# Peripherals.net
KiCad netlist of a schematic drawn in Altium Designer
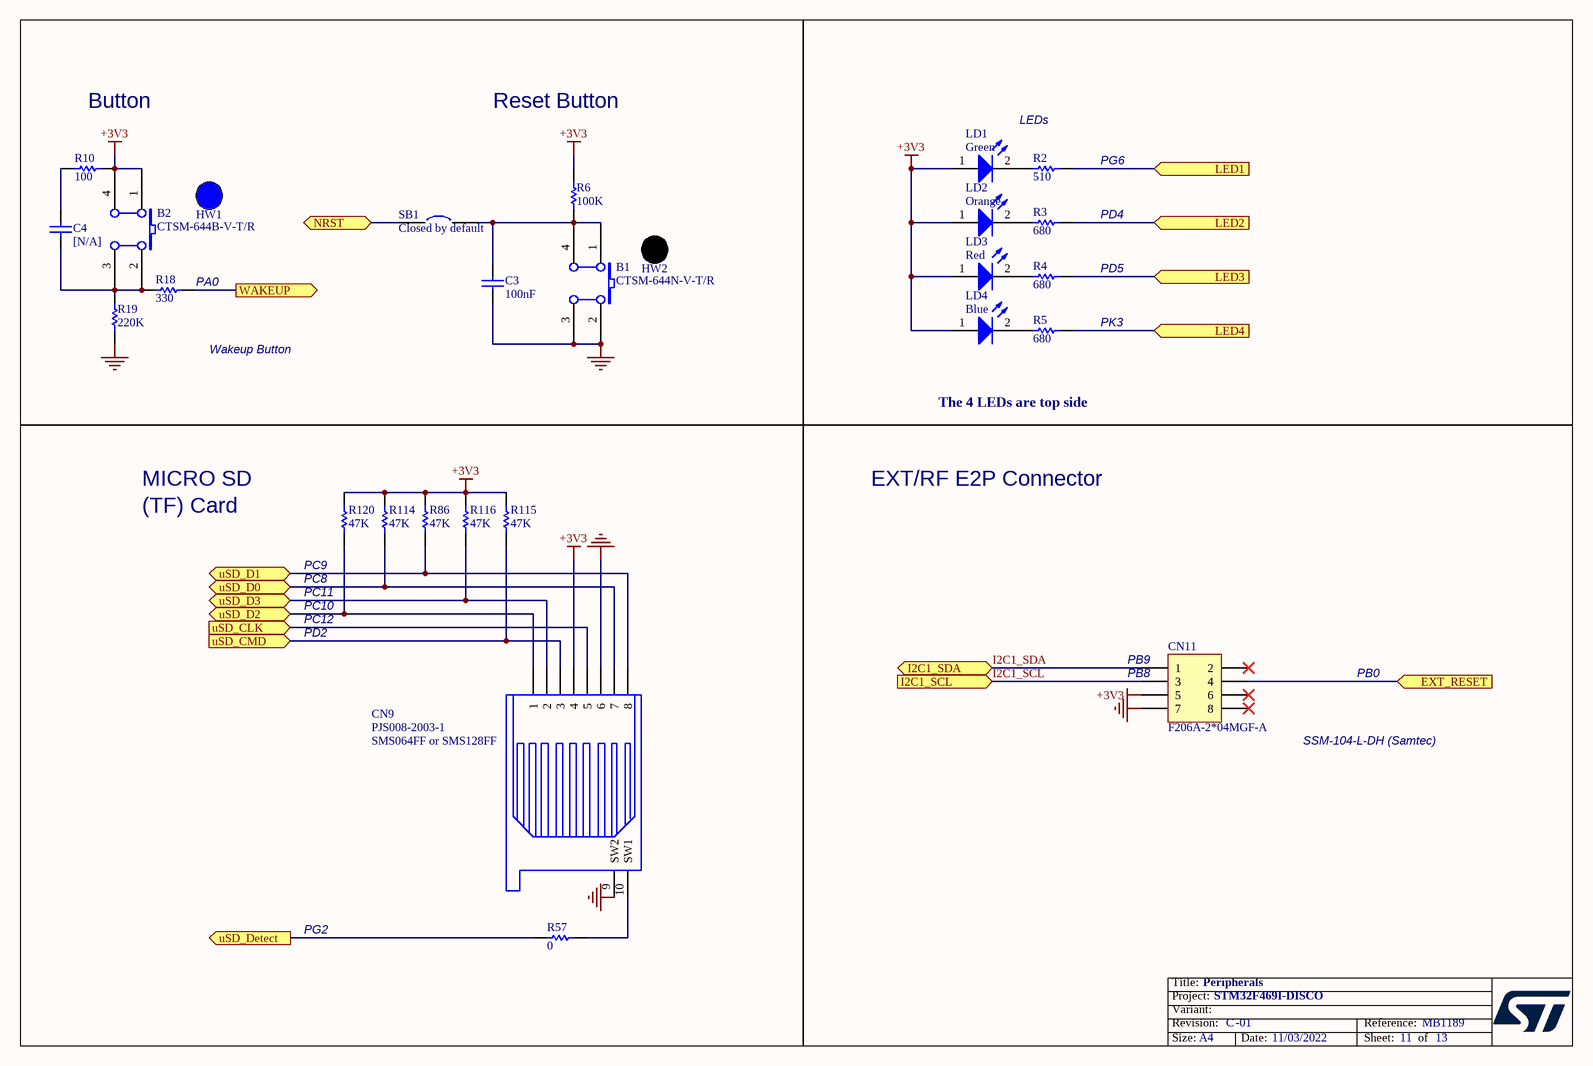
[diagram p0: Peripherals.SchDoc]

(export (version "E")
  (design (tool "Eeschema 10.0.6"))
  (components
    (comp (ref "B1")
      (value "CTSM-644N-V-T/R")
      (footprint "PB10")
      (description "Push-Button BLACK")
      (libsource (lib "MB1189") (part "SW PUSHBUTTON"))
    )
    (comp (ref "B2")
      (value "CTSM-644B-V-T/R")
      (footprint "PB10")
      (description "Push-Button BLUE")
      (libsource (lib "MB1189") (part "SW PUSHBUTTON"))
    )
    (comp (ref "C3")
      (value "100nF")
      (footprint "0402C")
      (description "Capacitor")
      (fields (field (name "PUBLISHER") "Altium Limited"))
      (libsource (lib "Miscellaneous Devices") (part "CAP"))
    )
    (comp (ref "C4")
      (value "[N/A]")
      (footprint "0603C")
      (description "Capacitor")
      (fields (field (name "PUBLISHER") "Altium Limited"))
      (libsource (lib "Miscellaneous Devices") (part "CAP"))
    )
    (comp (ref "CN9")
      (value "PJS008-2003-1")
      (footprint "MSD_PJS008_")
      (description "MicroSD Card Conn, Reversed-Type, Mnt Push-Push, Positionning holes")
      (libsource (lib "MB525") (part "SMS016AFA5E"))
    )
    (comp (ref "CN11")
      (value "F206A-2*04MGF-A")
      (footprint "SSM-104-L-DH")
      (description "Header, 4-Pin, Dual row")
      (fields (field (name "PUBLISHER") "Altium Limited"))
      (libsource (lib "mb1045") (part "SSM-104-L-DH"))
    )
    (comp (ref "HW1")
      (value "BUTTON_HAT_BLUE")
      (description "switch hat,blue")
      (libsource (lib "MB1189") (part "BUTTON_HAT_BLUE"))
    )
    (comp (ref "HW2")
      (value "BUTTON_HAT_BLACK")
      (description "switch hat,black")
      (libsource (lib "MB1189") (part "BUTTON_HAT_BLACK"))
    )
    (comp (ref "LD1")
      (value "Green")
      (footprint "0603D")
      (description "Typical RED, GREEN, YELLOW, AMBER GaAs LED")
      (fields (field (name "PUBLISHER") "Altium Limited"))
      (libsource (lib "Miscellaneous Devices") (part "LED2"))
    )
    (comp (ref "LD2")
      (value "Orange")
      (footprint "0603D")
      (description "Typical RED, GREEN, YELLOW, AMBER GaAs LED")
      (fields (field (name "PUBLISHER") "Altium Limited"))
      (libsource (lib "Miscellaneous Devices") (part "LED2"))
    )
    (comp (ref "LD3")
      (value "Red")
      (footprint "0603D")
      (description "Typical RED, GREEN, YELLOW, AMBER GaAs LED")
      (fields (field (name "PUBLISHER") "Altium Limited"))
      (libsource (lib "Miscellaneous Devices") (part "LED2"))
    )
    (comp (ref "LD4")
      (value "Blue")
      (footprint "0603D")
      (description "Typical RED, GREEN, YELLOW, AMBER GaAs LED")
      (fields (field (name "PUBLISHER") "Altium Limited"))
      (libsource (lib "Miscellaneous Devices") (part "LED2"))
    )
    (comp (ref "R2")
      (value "510")
      (footprint "0603R")
      (description "Resistor")
      (fields (field (name "PUBLISHER") "Altium Limited"))
      (libsource (lib "Miscellaneous Devices") (part "Res1"))
    )
    (comp (ref "R3")
      (value "680")
      (footprint "0603R")
      (description "Resistor")
      (fields (field (name "PUBLISHER") "Altium Limited"))
      (libsource (lib "Miscellaneous Devices") (part "Res1"))
    )
    (comp (ref "R4")
      (value "680")
      (footprint "0603R")
      (description "Resistor")
      (fields (field (name "PUBLISHER") "Altium Limited"))
      (libsource (lib "Miscellaneous Devices") (part "Res1"))
    )
    (comp (ref "R5")
      (value "680")
      (footprint "0603R")
      (description "Resistor")
      (fields (field (name "PUBLISHER") "Altium Limited"))
      (libsource (lib "Miscellaneous Devices") (part "Res1"))
    )
    (comp (ref "R6")
      (value "100K")
      (footprint "0603R")
      (description "Resistor")
      (fields (field (name "PUBLISHER") "Altium Limited"))
      (libsource (lib "Miscellaneous Devices") (part "res1"))
    )
    (comp (ref "R10")
      (value "100")
      (footprint "0603R")
      (description "Resistor")
      (fields (field (name "PUBLISHER") "Altium Limited"))
      (libsource (lib "Miscellaneous Devices") (part "Res1"))
    )
    (comp (ref "R18")
      (value "330")
      (footprint "0603R")
      (description "Resistor")
      (fields (field (name "PUBLISHER") "Altium Limited"))
      (libsource (lib "Miscellaneous Devices") (part "Res1"))
    )
    (comp (ref "R19")
      (value "220K")
      (footprint "0603R")
      (description "Resistor")
      (fields (field (name "PUBLISHER") "Altium Limited"))
      (libsource (lib "Miscellaneous Devices") (part "res1"))
    )
    (comp (ref "R57")
      (value "0")
      (footprint "0603R")
      (description "Resistor")
      (fields (field (name "PUBLISHER") "Altium Limited"))
      (libsource (lib "Miscellaneous Devices") (part "Res1"))
    )
    (comp (ref "R86")
      (value "47K")
      (footprint "0603R")
      (description "Resistor")
      (fields (field (name "PUBLISHER") "Altium Limited"))
      (libsource (lib "Miscellaneous Devices") (part "res1"))
    )
    (comp (ref "R114")
      (value "47K")
      (footprint "0603R")
      (description "Resistor")
      (fields (field (name "PUBLISHER") "Altium Limited"))
      (libsource (lib "Miscellaneous Devices") (part "res1"))
    )
    (comp (ref "R115")
      (value "47K")
      (footprint "0603R")
      (description "Resistor")
      (fields (field (name "PUBLISHER") "Altium Limited"))
      (libsource (lib "Miscellaneous Devices") (part "res1"))
    )
    (comp (ref "R116")
      (value "47K")
      (footprint "0603R")
      (description "Resistor")
      (fields (field (name "PUBLISHER") "Altium Limited"))
      (libsource (lib "Miscellaneous Devices") (part "res1"))
    )
    (comp (ref "R120")
      (value "47K")
      (footprint "0603R")
      (description "Resistor")
      (fields (field (name "PUBLISHER") "Altium Limited"))
      (libsource (lib "Miscellaneous Devices") (part "res1"))
    )
    (comp (ref "SB1")
      (value "Closed by default")
      (footprint "SB_0603")
      (description "Circuit Breaker")
      (fields (field (name "PUBLISHER") "Altium Limited"))
      (libsource (lib "Miscellaneous Devices") (part "Circuit Breaker"))
    )
  )
  (nets
    (net (code "1") (name "+3V3") (class "Default")
      (node (ref "B2") (pin "1") (pinfunction "A0_1") (pintype "passive"))
      (node (ref "B2") (pin "4") (pinfunction "A1_4") (pintype "passive"))
      (node (ref "CN11") (pin "5") (pinfunction "5_5") (pintype "passive"))
      (node (ref "CN9") (pin "4") (pinfunction "4_4") (pintype "passive"))
      (node (ref "LD1") (pin "1") (pinfunction "A_1") (pintype "passive"))
      (node (ref "LD2") (pin "1") (pinfunction "A_1") (pintype "passive"))
      (node (ref "LD3") (pin "1") (pinfunction "A_1") (pintype "passive"))
      (node (ref "LD4") (pin "1") (pinfunction "A_1") (pintype "passive"))
      (node (ref "R10") (pin "1") (pinfunction "1_1") (pintype "passive"))
      (node (ref "R114") (pin "1") (pinfunction "1_1") (pintype "passive"))
      (node (ref "R115") (pin "1") (pinfunction "1_1") (pintype "passive"))
      (node (ref "R116") (pin "1") (pinfunction "1_1") (pintype "passive"))
      (node (ref "R120") (pin "1") (pinfunction "1_1") (pintype "passive"))
      (node (ref "R6") (pin "1") (pinfunction "1_1") (pintype "passive"))
      (node (ref "R86") (pin "1") (pinfunction "1_1") (pintype "passive"))
    )
    (net (code "2") (name "/EXT_RESET") (class "Default")
      (node (ref "CN11") (pin "4") (pinfunction "4_4") (pintype "passive"))
    )
    (net (code "3") (name "/I2C1_SCL") (class "Default")
      (node (ref "CN11") (pin "3") (pinfunction "3_3") (pintype "passive"))
    )
    (net (code "4") (name "/I2C1_SDA") (class "Default")
      (node (ref "CN11") (pin "1") (pinfunction "1_1") (pintype "passive"))
    )
    (net (code "5") (name "/LED1") (class "Default")
      (node (ref "R2") (pin "1") (pinfunction "1_1") (pintype "passive"))
    )
    (net (code "6") (name "/LED2") (class "Default")
      (node (ref "R3") (pin "1") (pinfunction "1_1") (pintype "passive"))
    )
    (net (code "7") (name "/LED3") (class "Default")
      (node (ref "R4") (pin "1") (pinfunction "1_1") (pintype "passive"))
    )
    (net (code "8") (name "/LED4") (class "Default")
      (node (ref "R5") (pin "1") (pinfunction "1_1") (pintype "passive"))
    )
    (net (code "9") (name "/NRST") (class "Default")
      (node (ref "SB1") (pin "1") (pinfunction "1_1") (pintype "passive"))
    )
    (net (code "10") (name "/WAKEUP") (class "Default")
      (node (ref "R18") (pin "2") (pinfunction "2_2") (pintype "passive"))
    )
    (net (code "11") (name "/uSD_CLK") (class "Default")
      (node (ref "CN9") (pin "5") (pinfunction "5_5") (pintype "passive"))
    )
    (net (code "12") (name "/uSD_CMD") (class "Default")
      (node (ref "CN9") (pin "3") (pinfunction "3_3") (pintype "passive"))
      (node (ref "R115") (pin "2") (pinfunction "2_2") (pintype "passive"))
    )
    (net (code "13") (name "/uSD_D0") (class "Default")
      (node (ref "CN9") (pin "7") (pinfunction "7_7") (pintype "passive"))
      (node (ref "R114") (pin "2") (pinfunction "2_2") (pintype "passive"))
    )
    (net (code "14") (name "/uSD_D1") (class "Default")
      (node (ref "CN9") (pin "8") (pinfunction "8_8") (pintype "passive"))
      (node (ref "R86") (pin "2") (pinfunction "2_2") (pintype "passive"))
    )
    (net (code "15") (name "/uSD_D2") (class "Default")
      (node (ref "CN9") (pin "1") (pinfunction "1_1") (pintype "passive"))
      (node (ref "R120") (pin "2") (pinfunction "2_2") (pintype "passive"))
    )
    (net (code "16") (name "/uSD_D3") (class "Default")
      (node (ref "CN9") (pin "2") (pinfunction "2_2") (pintype "passive"))
      (node (ref "R116") (pin "2") (pinfunction "2_2") (pintype "passive"))
    )
    (net (code "17") (name "/uSD_Detect") (class "Default")
      (node (ref "R57") (pin "1") (pinfunction "1_1") (pintype "passive"))
    )
    (net (code "18") (name "GND") (class "Default")
      (node (ref "B1") (pin "2") (pinfunction "B0_2") (pintype "passive"))
      (node (ref "B1") (pin "3") (pinfunction "B1_3") (pintype "passive"))
      (node (ref "C3") (pin "1") (pinfunction "1_1") (pintype "passive"))
      (node (ref "CN11") (pin "7") (pinfunction "7_7") (pintype "passive"))
      (node (ref "CN9") (pin "6") (pinfunction "6_6") (pintype "passive"))
      (node (ref "CN9") (pin "9") (pinfunction "SW2_9") (pintype "passive"))
      (node (ref "R19") (pin "2") (pinfunction "2_2") (pintype "passive"))
    )
    (net (code "19") (name "Net-(B1-A0)") (class "Default")
      (node (ref "B1") (pin "1") (pinfunction "A0_1") (pintype "passive"))
      (node (ref "B1") (pin "4") (pinfunction "A1_4") (pintype "passive"))
      (node (ref "C3") (pin "2") (pinfunction "2_2") (pintype "passive"))
      (node (ref "R6") (pin "2") (pinfunction "2_2") (pintype "passive"))
      (node (ref "SB1") (pin "2") (pinfunction "2_2") (pintype "passive"))
    )
    (net (code "20") (name "Net-(B2-B0)") (class "Default")
      (node (ref "B2") (pin "2") (pinfunction "B0_2") (pintype "passive"))
      (node (ref "B2") (pin "3") (pinfunction "B1_3") (pintype "passive"))
      (node (ref "C4") (pin "2") (pinfunction "2_2") (pintype "passive"))
      (node (ref "R18") (pin "1") (pinfunction "1_1") (pintype "passive"))
      (node (ref "R19") (pin "1") (pinfunction "1_1") (pintype "passive"))
    )
    (net (code "21") (name "Net-(C4-Pad1)") (class "Default")
      (node (ref "C4") (pin "1") (pinfunction "1_1") (pintype "passive"))
      (node (ref "R10") (pin "2") (pinfunction "2_2") (pintype "passive"))
    )
    (net (code "22") (name "Net-(CN9-SW1)") (class "Default")
      (node (ref "CN9") (pin "10") (pinfunction "SW1_10") (pintype "passive"))
      (node (ref "R57") (pin "2") (pinfunction "2_2") (pintype "passive"))
    )
    (net (code "23") (name "Net-(LD1-K)") (class "Default")
      (node (ref "LD1") (pin "2") (pinfunction "K_2") (pintype "passive"))
      (node (ref "R2") (pin "2") (pinfunction "2_2") (pintype "passive"))
    )
    (net (code "24") (name "Net-(LD2-K)") (class "Default")
      (node (ref "LD2") (pin "2") (pinfunction "K_2") (pintype "passive"))
      (node (ref "R3") (pin "2") (pinfunction "2_2") (pintype "passive"))
    )
    (net (code "25") (name "Net-(LD3-K)") (class "Default")
      (node (ref "LD3") (pin "2") (pinfunction "K_2") (pintype "passive"))
      (node (ref "R4") (pin "2") (pinfunction "2_2") (pintype "passive"))
    )
    (net (code "26") (name "Net-(LD4-K)") (class "Default")
      (node (ref "LD4") (pin "2") (pinfunction "K_2") (pintype "passive"))
      (node (ref "R5") (pin "2") (pinfunction "2_2") (pintype "passive"))
    )
    (net (code "27") (name "unconnected-(CN11-Pad2)") (class "Default")
      (node (ref "CN11") (pin "2") (pinfunction "2_2") (pintype "passive+no_connect"))
    )
    (net (code "28") (name "unconnected-(CN11-Pad6)") (class "Default")
      (node (ref "CN11") (pin "6") (pinfunction "6_6") (pintype "passive+no_connect"))
    )
    (net (code "29") (name "unconnected-(CN11-Pad8)") (class "Default")
      (node (ref "CN11") (pin "8") (pinfunction "8_8") (pintype "passive+no_connect"))
    )
  )
)
